# sx1509-breakout_mount.net
KiCad netlist of a schematic drawn in EAGLE
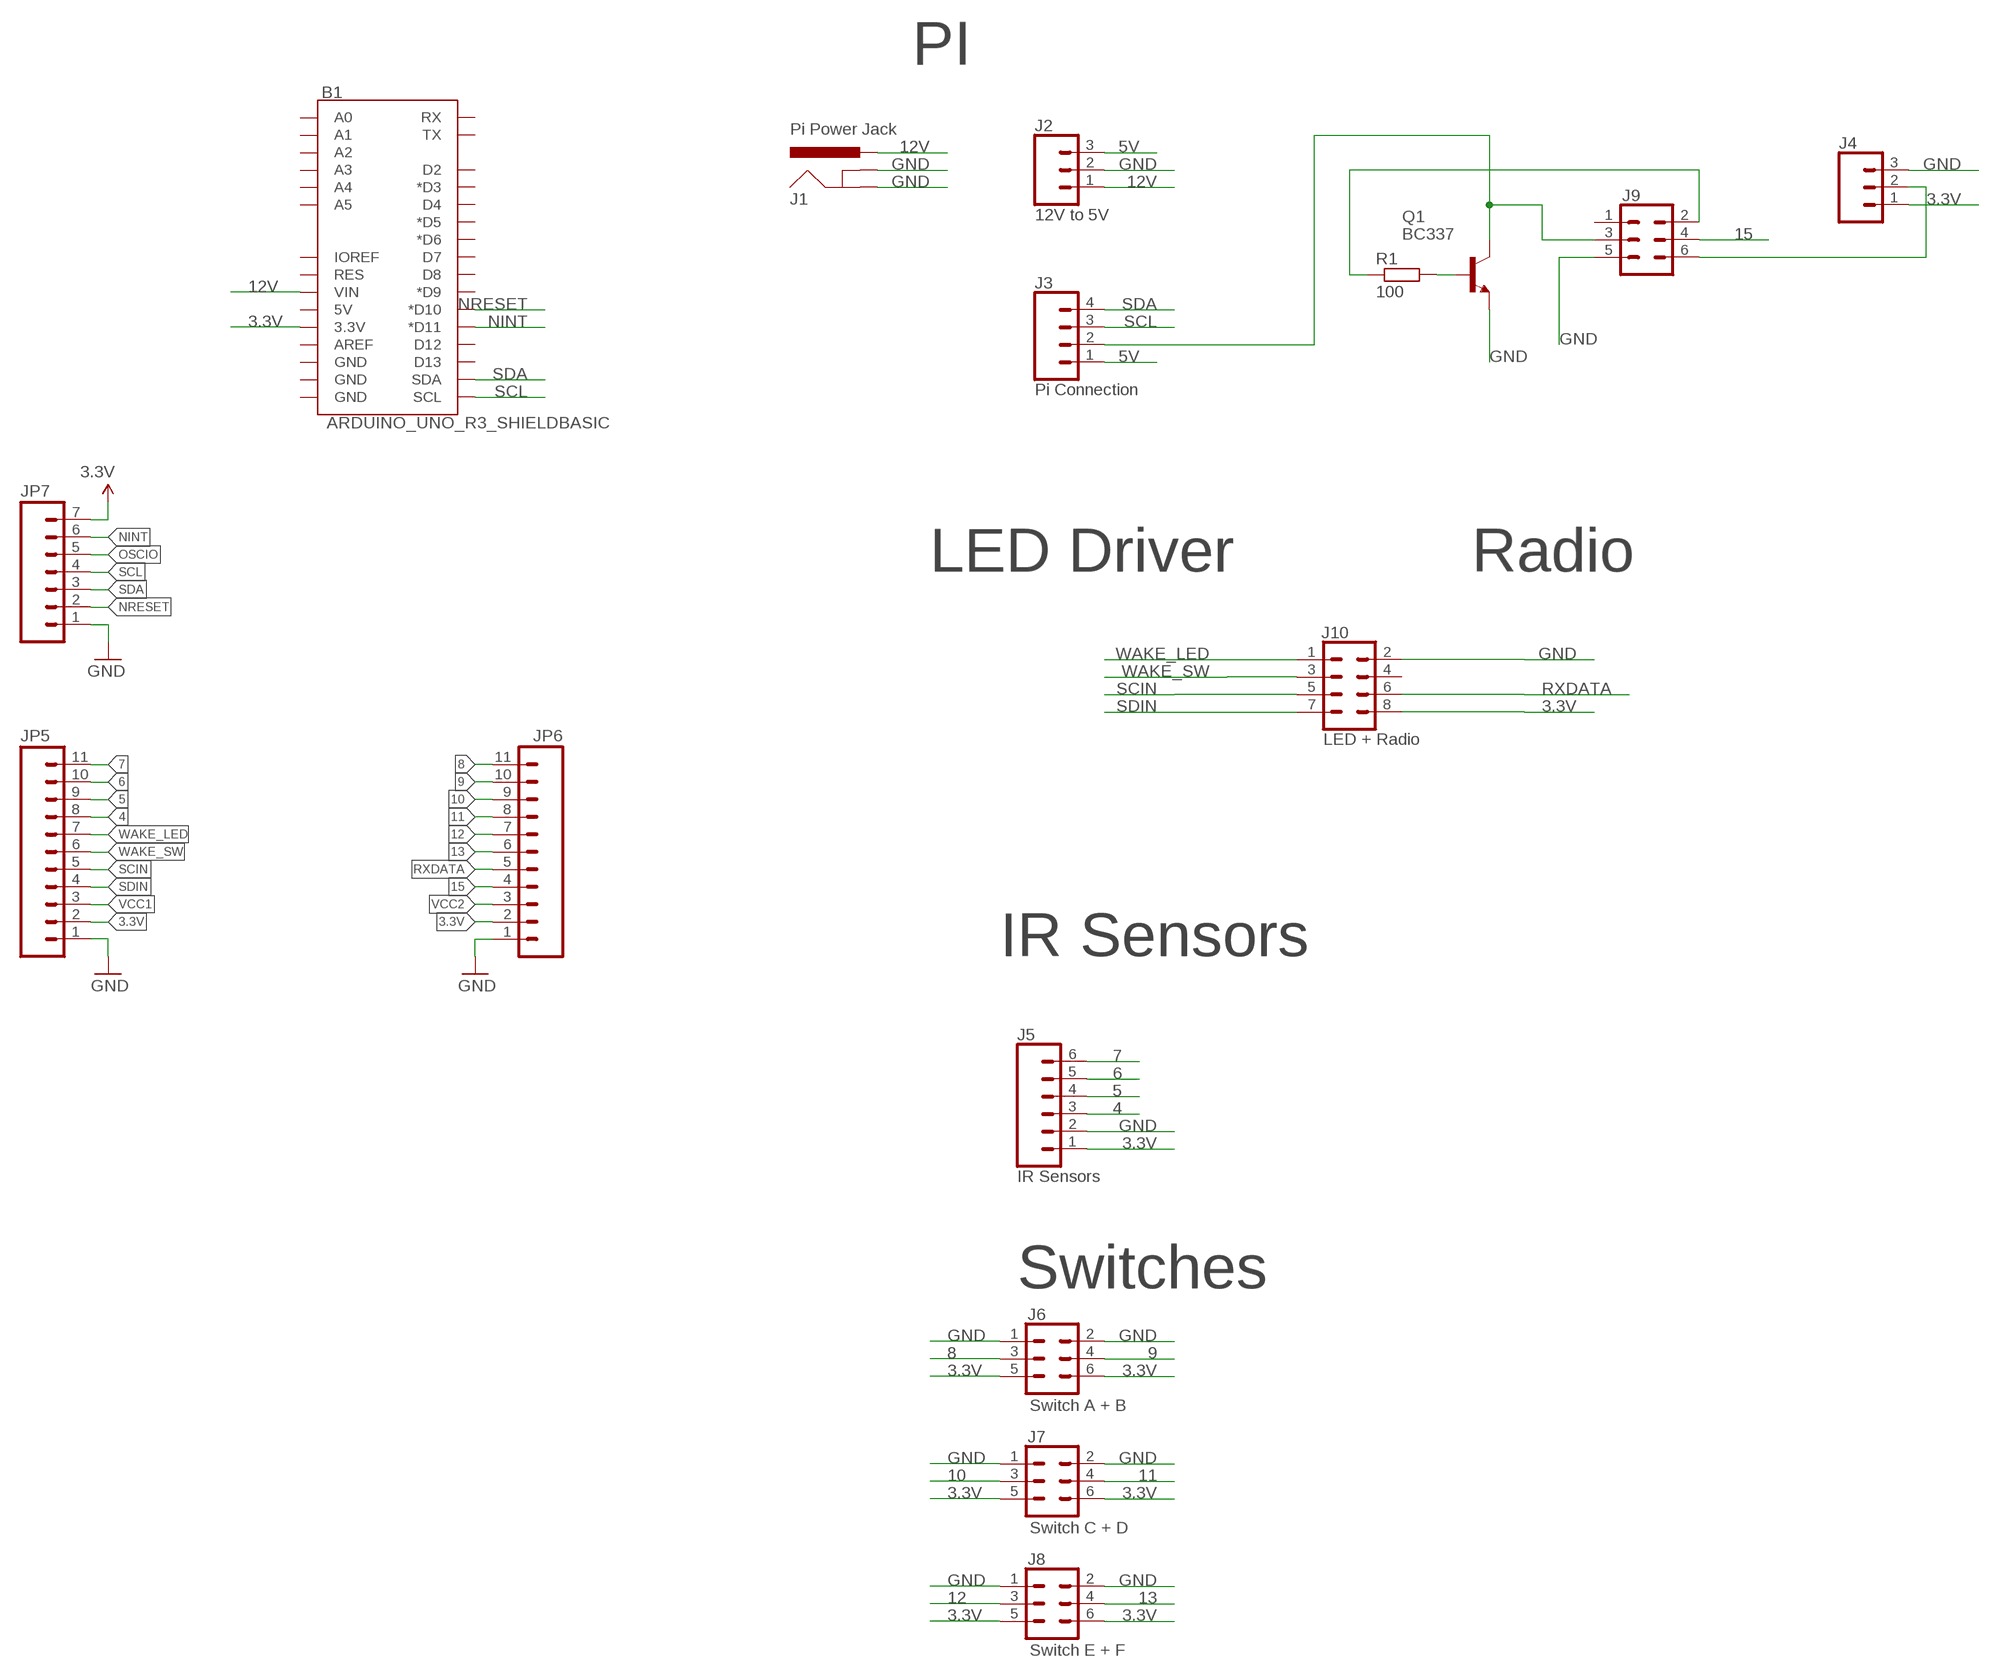
[diagram p0: schematic, sheet 1]

(export (version "E")
  (design (tool "Eeschema 10.0.6"))
  (components
    (comp (ref "B1")
      (value "ARDUINO_UNO_R3_SHIELDBASIC")
      (footprint "eagle-import:UNO_R3_SHIELD")
      (libsource (lib "eagle-import") (part "ARDUINO_UNO_R3_SHIELDBASIC"))
    )
    (comp (ref "J1")
      (value "Pi Power Jack")
      (footprint "eagle-import:POWER_JACK_PTH_BREAD")
      (libsource (lib "eagle-import") (part "POWER_JACKPTH_BREAD"))
    )
    (comp (ref "J2")
      (value "12V to 5V")
      (footprint "eagle-import:1X03")
      (libsource (lib "eagle-import") (part "CONN_03"))
    )
    (comp (ref "J3")
      (value "Pi Connection")
      (footprint "eagle-import:1X04")
      (libsource (lib "eagle-import") (part "CONN_04"))
    )
    (comp (ref "J4")
      (value "CONN_03")
      (footprint "eagle-import:1X03")
      (libsource (lib "eagle-import") (part "CONN_03"))
    )
    (comp (ref "J5")
      (value "IR Sensors")
      (footprint "eagle-import:1X06")
      (libsource (lib "eagle-import") (part "CONN_06SILK_FEMALE_PTH"))
    )
    (comp (ref "J6")
      (value "Switch A + B")
      (footprint "eagle-import:2X3")
      (libsource (lib "eagle-import") (part "CONN_03X2FEMALE"))
    )
    (comp (ref "J7")
      (value "Switch C + D")
      (footprint "eagle-import:2X3")
      (libsource (lib "eagle-import") (part "CONN_03X2FEMALE"))
    )
    (comp (ref "J8")
      (value "Switch E + F")
      (footprint "eagle-import:2X3")
      (libsource (lib "eagle-import") (part "CONN_03X2FEMALE"))
    )
    (comp (ref "J9")
      (value "CONN_03X2NO_SILK")
      (footprint "eagle-import:2X3-NS")
      (libsource (lib "eagle-import") (part "CONN_03X2NO_SILK"))
    )
    (comp (ref "J10")
      (value "LED + Radio")
      (footprint "eagle-import:2X4")
      (libsource (lib "eagle-import") (part "CONN_04X2"))
    )
    (comp (ref "JP5")
      (value "M111X11_NO_SILK")
      (footprint "eagle-import:1X11_NO_SILK")
      (libsource (lib "eagle-import") (part "M111X11_NO_SILK"))
    )
    (comp (ref "JP6")
      (value "M111X11_NO_SILK")
      (footprint "eagle-import:1X11_NO_SILK")
      (libsource (lib "eagle-import") (part "M111X11_NO_SILK"))
    )
    (comp (ref "JP7")
      (value "M07")
      (footprint "eagle-import:1X07")
      (libsource (lib "eagle-import") (part "M07"))
    )
    (comp (ref "Q1")
      (value "BC337")
      (footprint "eagle-import:TO92")
      (libsource (lib "eagle-import") (part "BC337"))
    )
    (comp (ref "R1")
      (value "100")
      (footprint "eagle-import:0204_7")
      (libsource (lib "eagle-import") (part "R0204/7"))
    )
  )
  (nets
    (net (code "1") (name "/5V") (class "Default")
      (node (ref "J2") (pin "3") (pinfunction "3_3") (pintype "passive"))
      (node (ref "J3") (pin "1") (pinfunction "1_1") (pintype "passive"))
    )
    (net (code "2") (name "/12V") (class "Default")
      (node (ref "B1") (pin "VIN") (pinfunction "VIN_VIN") (pintype "bidirectional"))
      (node (ref "J1") (pin "PWR") (pinfunction "PWR_PWR") (pintype "bidirectional"))
      (node (ref "J2") (pin "1") (pinfunction "1_1") (pintype "passive"))
    )
    (net (code "3") (name "3.3V") (class "Default")
      (node (ref "B1") (pin "3.3V") (pinfunction "3.3V_3.3V") (pintype "bidirectional"))
      (node (ref "J10") (pin "8") (pinfunction "8_8") (pintype "passive"))
      (node (ref "J4") (pin "1") (pinfunction "1_1") (pintype "passive"))
      (node (ref "J5") (pin "1") (pinfunction "1_1") (pintype "passive"))
      (node (ref "J6") (pin "5") (pinfunction "5_5") (pintype "bidirectional"))
      (node (ref "J6") (pin "6") (pinfunction "6_6") (pintype "bidirectional"))
      (node (ref "J7") (pin "5") (pinfunction "5_5") (pintype "bidirectional"))
      (node (ref "J7") (pin "6") (pinfunction "6_6") (pintype "bidirectional"))
      (node (ref "J8") (pin "5") (pinfunction "5_5") (pintype "bidirectional"))
      (node (ref "J8") (pin "6") (pinfunction "6_6") (pintype "bidirectional"))
      (node (ref "JP5") (pin "2") (pinfunction "2_2") (pintype "passive"))
      (node (ref "JP6") (pin "2") (pinfunction "2_2") (pintype "passive"))
      (node (ref "JP7") (pin "7") (pinfunction "7_7") (pintype "passive"))
    )
    (net (code "4") (name "4") (class "Default")
      (node (ref "J5") (pin "3") (pinfunction "3_3") (pintype "passive"))
      (node (ref "JP5") (pin "8") (pinfunction "8_8") (pintype "passive"))
    )
    (net (code "5") (name "5") (class "Default")
      (node (ref "J5") (pin "4") (pinfunction "4_4") (pintype "passive"))
      (node (ref "JP5") (pin "9") (pinfunction "9_9") (pintype "passive"))
    )
    (net (code "6") (name "6") (class "Default")
      (node (ref "J5") (pin "5") (pinfunction "5_5") (pintype "passive"))
      (node (ref "JP5") (pin "10") (pinfunction "10_10") (pintype "passive"))
    )
    (net (code "7") (name "7") (class "Default")
      (node (ref "J5") (pin "6") (pinfunction "6_6") (pintype "passive"))
      (node (ref "JP5") (pin "11") (pinfunction "11_11") (pintype "passive"))
    )
    (net (code "8") (name "8") (class "Default")
      (node (ref "J6") (pin "3") (pinfunction "3_3") (pintype "bidirectional"))
      (node (ref "JP6") (pin "11") (pinfunction "11_11") (pintype "passive"))
    )
    (net (code "9") (name "9") (class "Default")
      (node (ref "J6") (pin "4") (pinfunction "4_4") (pintype "bidirectional"))
      (node (ref "JP6") (pin "10") (pinfunction "10_10") (pintype "passive"))
    )
    (net (code "10") (name "10") (class "Default")
      (node (ref "J7") (pin "3") (pinfunction "3_3") (pintype "bidirectional"))
      (node (ref "JP6") (pin "9") (pinfunction "9_9") (pintype "passive"))
    )
    (net (code "11") (name "11") (class "Default")
      (node (ref "J7") (pin "4") (pinfunction "4_4") (pintype "bidirectional"))
      (node (ref "JP6") (pin "8") (pinfunction "8_8") (pintype "passive"))
    )
    (net (code "12") (name "12") (class "Default")
      (node (ref "J8") (pin "3") (pinfunction "3_3") (pintype "bidirectional"))
      (node (ref "JP6") (pin "7") (pinfunction "7_7") (pintype "passive"))
    )
    (net (code "13") (name "13") (class "Default")
      (node (ref "J8") (pin "4") (pinfunction "4_4") (pintype "bidirectional"))
      (node (ref "JP6") (pin "6") (pinfunction "6_6") (pintype "passive"))
    )
    (net (code "14") (name "15") (class "Default")
      (node (ref "J9") (pin "4") (pinfunction "4_4") (pintype "bidirectional"))
      (node (ref "JP6") (pin "4") (pinfunction "4_4") (pintype "passive"))
    )
    (net (code "15") (name "GND") (class "Default")
      (node (ref "J1") (pin "GND") (pinfunction "GND_GND") (pintype "bidirectional"))
      (node (ref "J1") (pin "GNDBREAK") (pinfunction "GNDBREAK_GNDBREAK") (pintype "bidirectional"))
      (node (ref "J10") (pin "2") (pinfunction "2_2") (pintype "passive"))
      (node (ref "J2") (pin "2") (pinfunction "2_2") (pintype "passive"))
      (node (ref "J4") (pin "3") (pinfunction "3_3") (pintype "passive"))
      (node (ref "J5") (pin "2") (pinfunction "2_2") (pintype "passive"))
      (node (ref "J6") (pin "1") (pinfunction "1_1") (pintype "bidirectional"))
      (node (ref "J6") (pin "2") (pinfunction "2_2") (pintype "bidirectional"))
      (node (ref "J7") (pin "1") (pinfunction "1_1") (pintype "bidirectional"))
      (node (ref "J7") (pin "2") (pinfunction "2_2") (pintype "bidirectional"))
      (node (ref "J8") (pin "1") (pinfunction "1_1") (pintype "bidirectional"))
      (node (ref "J8") (pin "2") (pinfunction "2_2") (pintype "bidirectional"))
      (node (ref "J9") (pin "5") (pinfunction "5_5") (pintype "bidirectional"))
      (node (ref "JP5") (pin "1") (pinfunction "1_1") (pintype "passive"))
      (node (ref "JP6") (pin "1") (pinfunction "1_1") (pintype "passive"))
      (node (ref "JP7") (pin "1") (pinfunction "1_1") (pintype "passive"))
      (node (ref "Q1") (pin "1") (pinfunction "E_1") (pintype "passive"))
    )
    (net (code "16") (name "NINT") (class "Default")
      (node (ref "B1") (pin "D11") (pinfunction "*D11_D11") (pintype "bidirectional"))
      (node (ref "JP7") (pin "6") (pinfunction "6_6") (pintype "passive"))
    )
    (net (code "17") (name "NRESET") (class "Default")
      (node (ref "B1") (pin "D10") (pinfunction "*D10_D10") (pintype "bidirectional"))
      (node (ref "JP7") (pin "2") (pinfunction "2_2") (pintype "passive"))
    )
    (net (code "18") (name "Net-(J4-Pad2)") (class "Default")
      (node (ref "J4") (pin "2") (pinfunction "2_2") (pintype "passive"))
      (node (ref "J9") (pin "6") (pinfunction "6_6") (pintype "bidirectional"))
    )
    (net (code "19") (name "Net-(J9-Pad2)") (class "Default")
      (node (ref "J9") (pin "2") (pinfunction "2_2") (pintype "bidirectional"))
      (node (ref "R1") (pin "1") (pinfunction "1_1") (pintype "passive"))
    )
    (net (code "20") (name "Net-(Q1-B)") (class "Default")
      (node (ref "Q1") (pin "2") (pinfunction "B_2") (pintype "passive"))
      (node (ref "R1") (pin "2") (pinfunction "2_2") (pintype "passive"))
    )
    (net (code "21") (name "Net-(Q1-C)") (class "Default")
      (node (ref "J3") (pin "2") (pinfunction "2_2") (pintype "passive"))
      (node (ref "J9") (pin "3") (pinfunction "3_3") (pintype "bidirectional"))
      (node (ref "Q1") (pin "3") (pinfunction "C_3") (pintype "passive"))
    )
    (net (code "22") (name "OSCIO") (class "Default")
      (node (ref "JP7") (pin "5") (pinfunction "5_5") (pintype "passive"))
    )
    (net (code "23") (name "RXDATA") (class "Default")
      (node (ref "J10") (pin "6") (pinfunction "6_6") (pintype "passive"))
      (node (ref "JP6") (pin "5") (pinfunction "5_5") (pintype "passive"))
    )
    (net (code "24") (name "SCIN") (class "Default")
      (node (ref "J10") (pin "5") (pinfunction "5_5") (pintype "passive"))
      (node (ref "JP5") (pin "5") (pinfunction "5_5") (pintype "passive"))
    )
    (net (code "25") (name "SCL") (class "Default")
      (node (ref "B1") (pin "SCL") (pinfunction "SCL_SCL") (pintype "bidirectional"))
      (node (ref "J3") (pin "3") (pinfunction "3_3") (pintype "passive"))
      (node (ref "JP7") (pin "4") (pinfunction "4_4") (pintype "passive"))
    )
    (net (code "26") (name "SDA") (class "Default")
      (node (ref "B1") (pin "SDA") (pinfunction "SDA_SDA") (pintype "bidirectional"))
      (node (ref "J3") (pin "4") (pinfunction "4_4") (pintype "passive"))
      (node (ref "JP7") (pin "3") (pinfunction "3_3") (pintype "passive"))
    )
    (net (code "27") (name "SDIN") (class "Default")
      (node (ref "J10") (pin "7") (pinfunction "7_7") (pintype "passive"))
      (node (ref "JP5") (pin "4") (pinfunction "4_4") (pintype "passive"))
    )
    (net (code "28") (name "VCC1") (class "Default")
      (node (ref "JP5") (pin "3") (pinfunction "3_3") (pintype "passive"))
    )
    (net (code "29") (name "VCC2") (class "Default")
      (node (ref "JP6") (pin "3") (pinfunction "3_3") (pintype "passive"))
    )
    (net (code "30") (name "WAKE_LED") (class "Default")
      (node (ref "J10") (pin "1") (pinfunction "1_1") (pintype "passive"))
      (node (ref "JP5") (pin "7") (pinfunction "7_7") (pintype "passive"))
    )
    (net (code "31") (name "WAKE_SW") (class "Default")
      (node (ref "J10") (pin "3") (pinfunction "3_3") (pintype "passive"))
      (node (ref "JP5") (pin "6") (pinfunction "6_6") (pintype "passive"))
    )
    (net (code "32") (name "unconnected-(B1-*D3-PadD3)") (class "Default")
      (node (ref "B1") (pin "D3") (pinfunction "*D3_D3") (pintype "bidirectional"))
    )
    (net (code "33") (name "unconnected-(B1-*D5-PadD5)") (class "Default")
      (node (ref "B1") (pin "D5") (pinfunction "*D5_D5") (pintype "bidirectional"))
    )
    (net (code "34") (name "unconnected-(B1-*D6-PadD6)") (class "Default")
      (node (ref "B1") (pin "D6") (pinfunction "*D6_D6") (pintype "bidirectional"))
    )
    (net (code "35") (name "unconnected-(B1-*D9-PadD9)") (class "Default")
      (node (ref "B1") (pin "D9") (pinfunction "*D9_D9") (pintype "bidirectional"))
    )
    (net (code "36") (name "unconnected-(B1-GND-PadGND@0)") (class "Default")
      (node (ref "B1") (pin "GND@0") (pinfunction "GND_GND@0") (pintype "bidirectional"))
    )
    (net (code "37") (name "unconnected-(B1-GND-PadGND@1)") (class "Default")
      (node (ref "B1") (pin "GND@1") (pinfunction "GND_GND@1") (pintype "bidirectional"))
    )
    (net (code "38") (name "unconnected-(B1-GND-PadGND@2)") (class "Default")
      (node (ref "B1") (pin "GND@2") (pinfunction "GND_GND@2") (pintype "bidirectional"))
    )
    (net (code "39") (name "unconnected-(B1-Pad5V)") (class "Default")
      (node (ref "B1") (pin "5V") (pinfunction "5V_5V") (pintype "bidirectional"))
    )
    (net (code "40") (name "unconnected-(B1-PadA0)") (class "Default")
      (node (ref "B1") (pin "A0") (pinfunction "A0_A0") (pintype "bidirectional"))
    )
    (net (code "41") (name "unconnected-(B1-PadA1)") (class "Default")
      (node (ref "B1") (pin "A1") (pinfunction "A1_A1") (pintype "bidirectional"))
    )
    (net (code "42") (name "unconnected-(B1-PadA2)") (class "Default")
      (node (ref "B1") (pin "A2") (pinfunction "A2_A2") (pintype "bidirectional"))
    )
    (net (code "43") (name "unconnected-(B1-PadA3)") (class "Default")
      (node (ref "B1") (pin "A3") (pinfunction "A3_A3") (pintype "bidirectional"))
    )
    (net (code "44") (name "unconnected-(B1-PadA4)") (class "Default")
      (node (ref "B1") (pin "A4") (pinfunction "A4_A4") (pintype "bidirectional"))
    )
    (net (code "45") (name "unconnected-(B1-PadA5)") (class "Default")
      (node (ref "B1") (pin "A5") (pinfunction "A5_A5") (pintype "bidirectional"))
    )
    (net (code "46") (name "unconnected-(B1-PadAREF)") (class "Default")
      (node (ref "B1") (pin "AREF") (pinfunction "AREF_AREF") (pintype "bidirectional"))
    )
    (net (code "47") (name "unconnected-(B1-PadD2)") (class "Default")
      (node (ref "B1") (pin "D2") (pinfunction "D2_D2") (pintype "bidirectional"))
    )
    (net (code "48") (name "unconnected-(B1-PadD4)") (class "Default")
      (node (ref "B1") (pin "D4") (pinfunction "D4_D4") (pintype "bidirectional"))
    )
    (net (code "49") (name "unconnected-(B1-PadD7)") (class "Default")
      (node (ref "B1") (pin "D7") (pinfunction "D7_D7") (pintype "bidirectional"))
    )
    (net (code "50") (name "unconnected-(B1-PadD8)") (class "Default")
      (node (ref "B1") (pin "D8") (pinfunction "D8_D8") (pintype "bidirectional"))
    )
    (net (code "51") (name "unconnected-(B1-PadD12)") (class "Default")
      (node (ref "B1") (pin "D12") (pinfunction "D12_D12") (pintype "bidirectional"))
    )
    (net (code "52") (name "unconnected-(B1-PadD13)") (class "Default")
      (node (ref "B1") (pin "D13") (pinfunction "D13_D13") (pintype "bidirectional"))
    )
    (net (code "53") (name "unconnected-(B1-PadIOREF)") (class "Default")
      (node (ref "B1") (pin "IOREF") (pinfunction "IOREF_IOREF") (pintype "bidirectional"))
    )
    (net (code "54") (name "unconnected-(B1-PadRES)") (class "Default")
      (node (ref "B1") (pin "RES") (pinfunction "RES_RES") (pintype "bidirectional"))
    )
    (net (code "55") (name "unconnected-(B1-PadRX)") (class "Default")
      (node (ref "B1") (pin "RX") (pinfunction "RX_RX") (pintype "bidirectional"))
    )
    (net (code "56") (name "unconnected-(B1-PadTX)") (class "Default")
      (node (ref "B1") (pin "TX") (pinfunction "TX_TX") (pintype "bidirectional"))
    )
    (net (code "57") (name "unconnected-(J9-Pad1)") (class "Default")
      (node (ref "J9") (pin "1") (pinfunction "1_1") (pintype "bidirectional"))
    )
    (net (code "58") (name "unconnected-(J10-Pad4)") (class "Default")
      (node (ref "J10") (pin "4") (pinfunction "4_4") (pintype "passive"))
    )
  )
)
